# pinchy.net
KiCad netlist of a schematic drawn in EAGLE
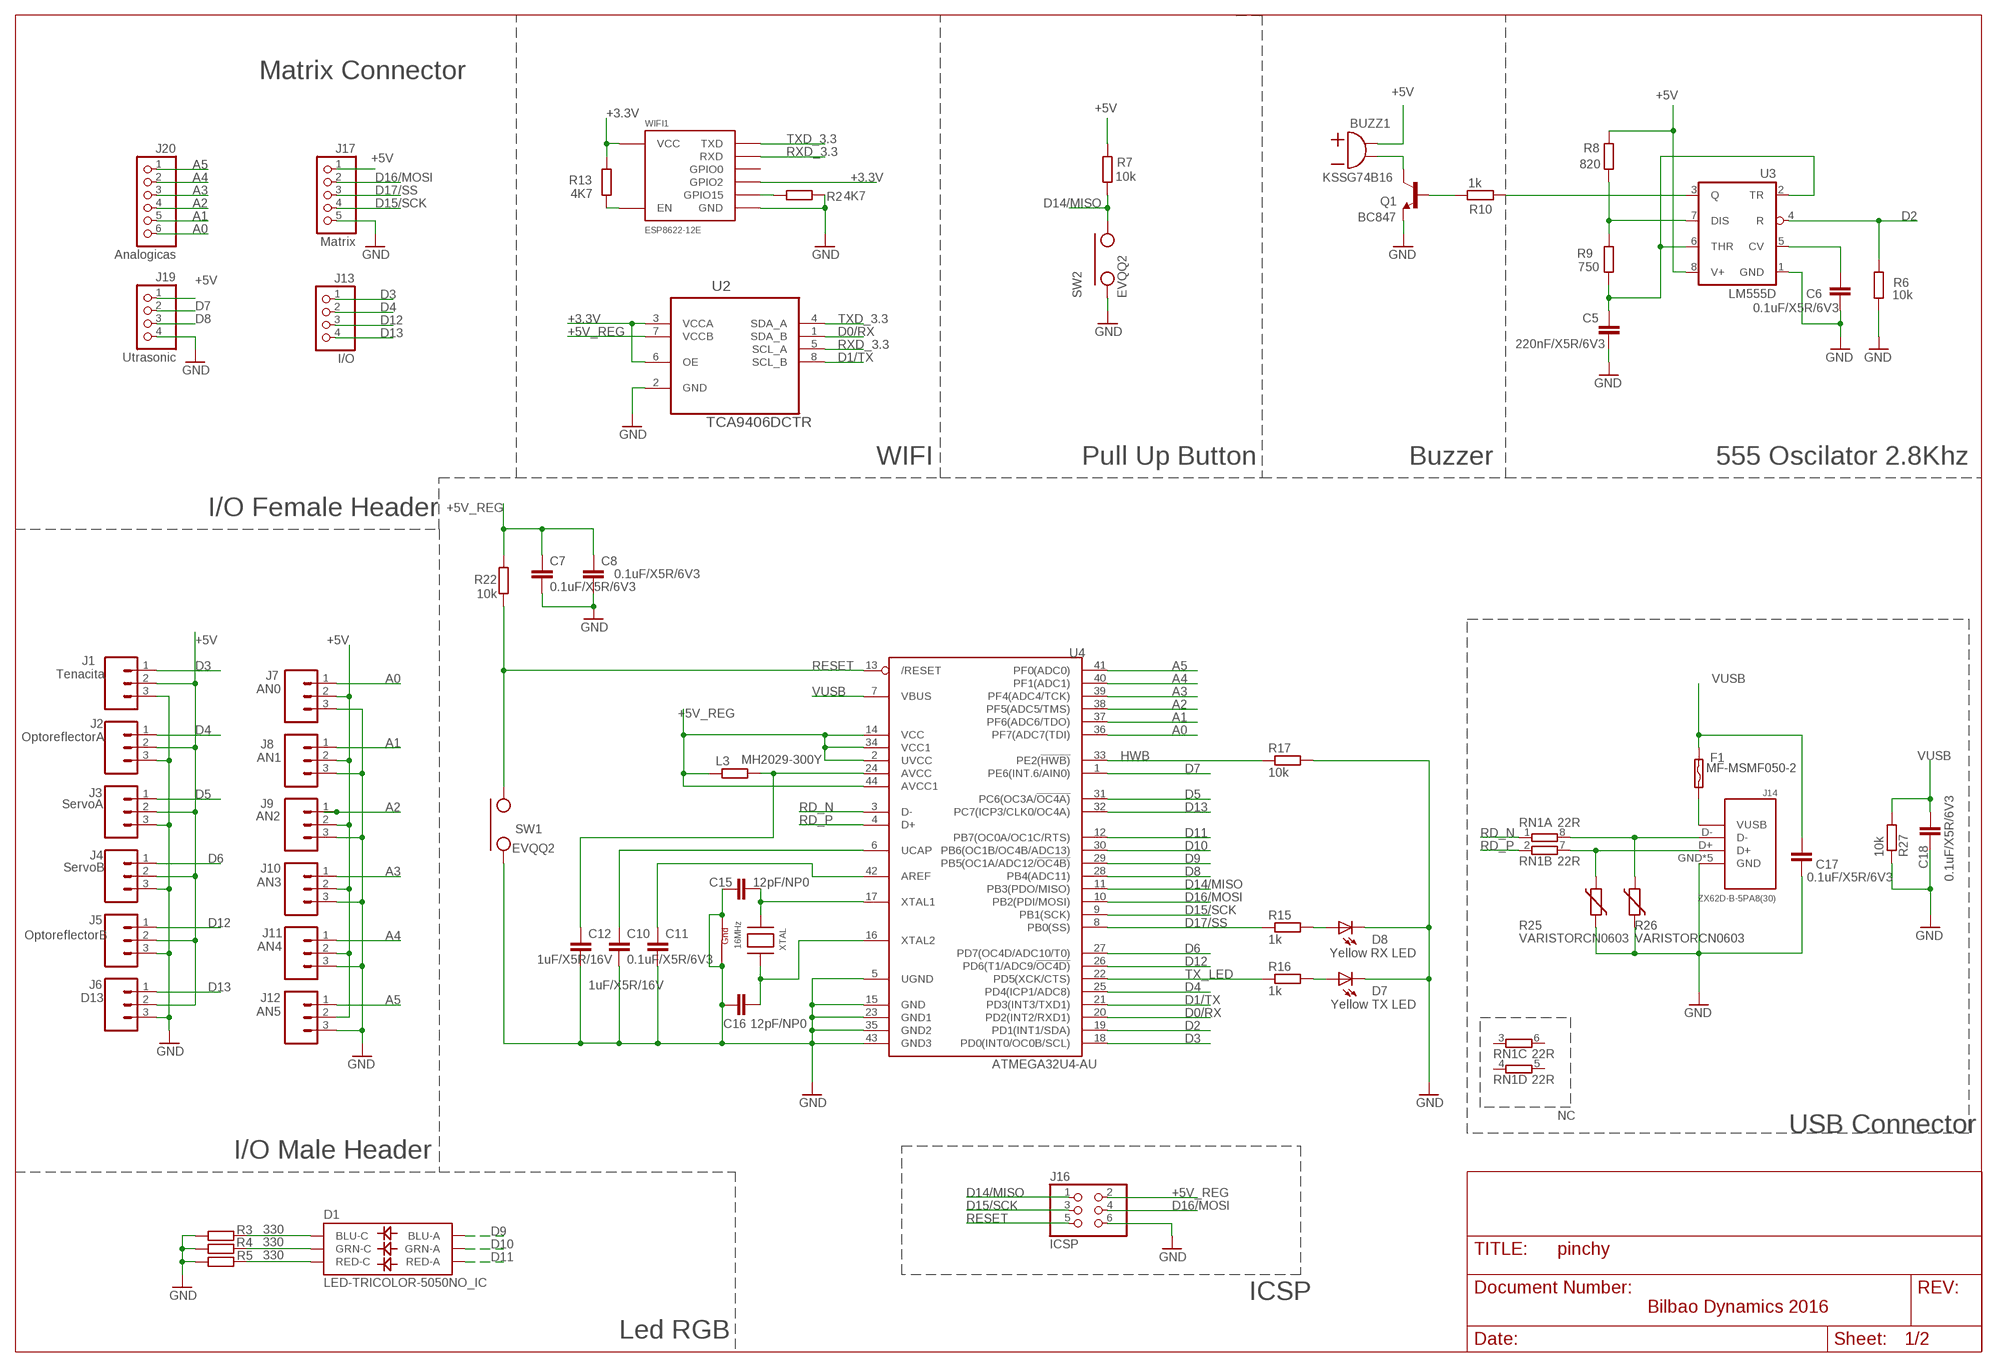
[diagram p0: schematic, sheet 1]
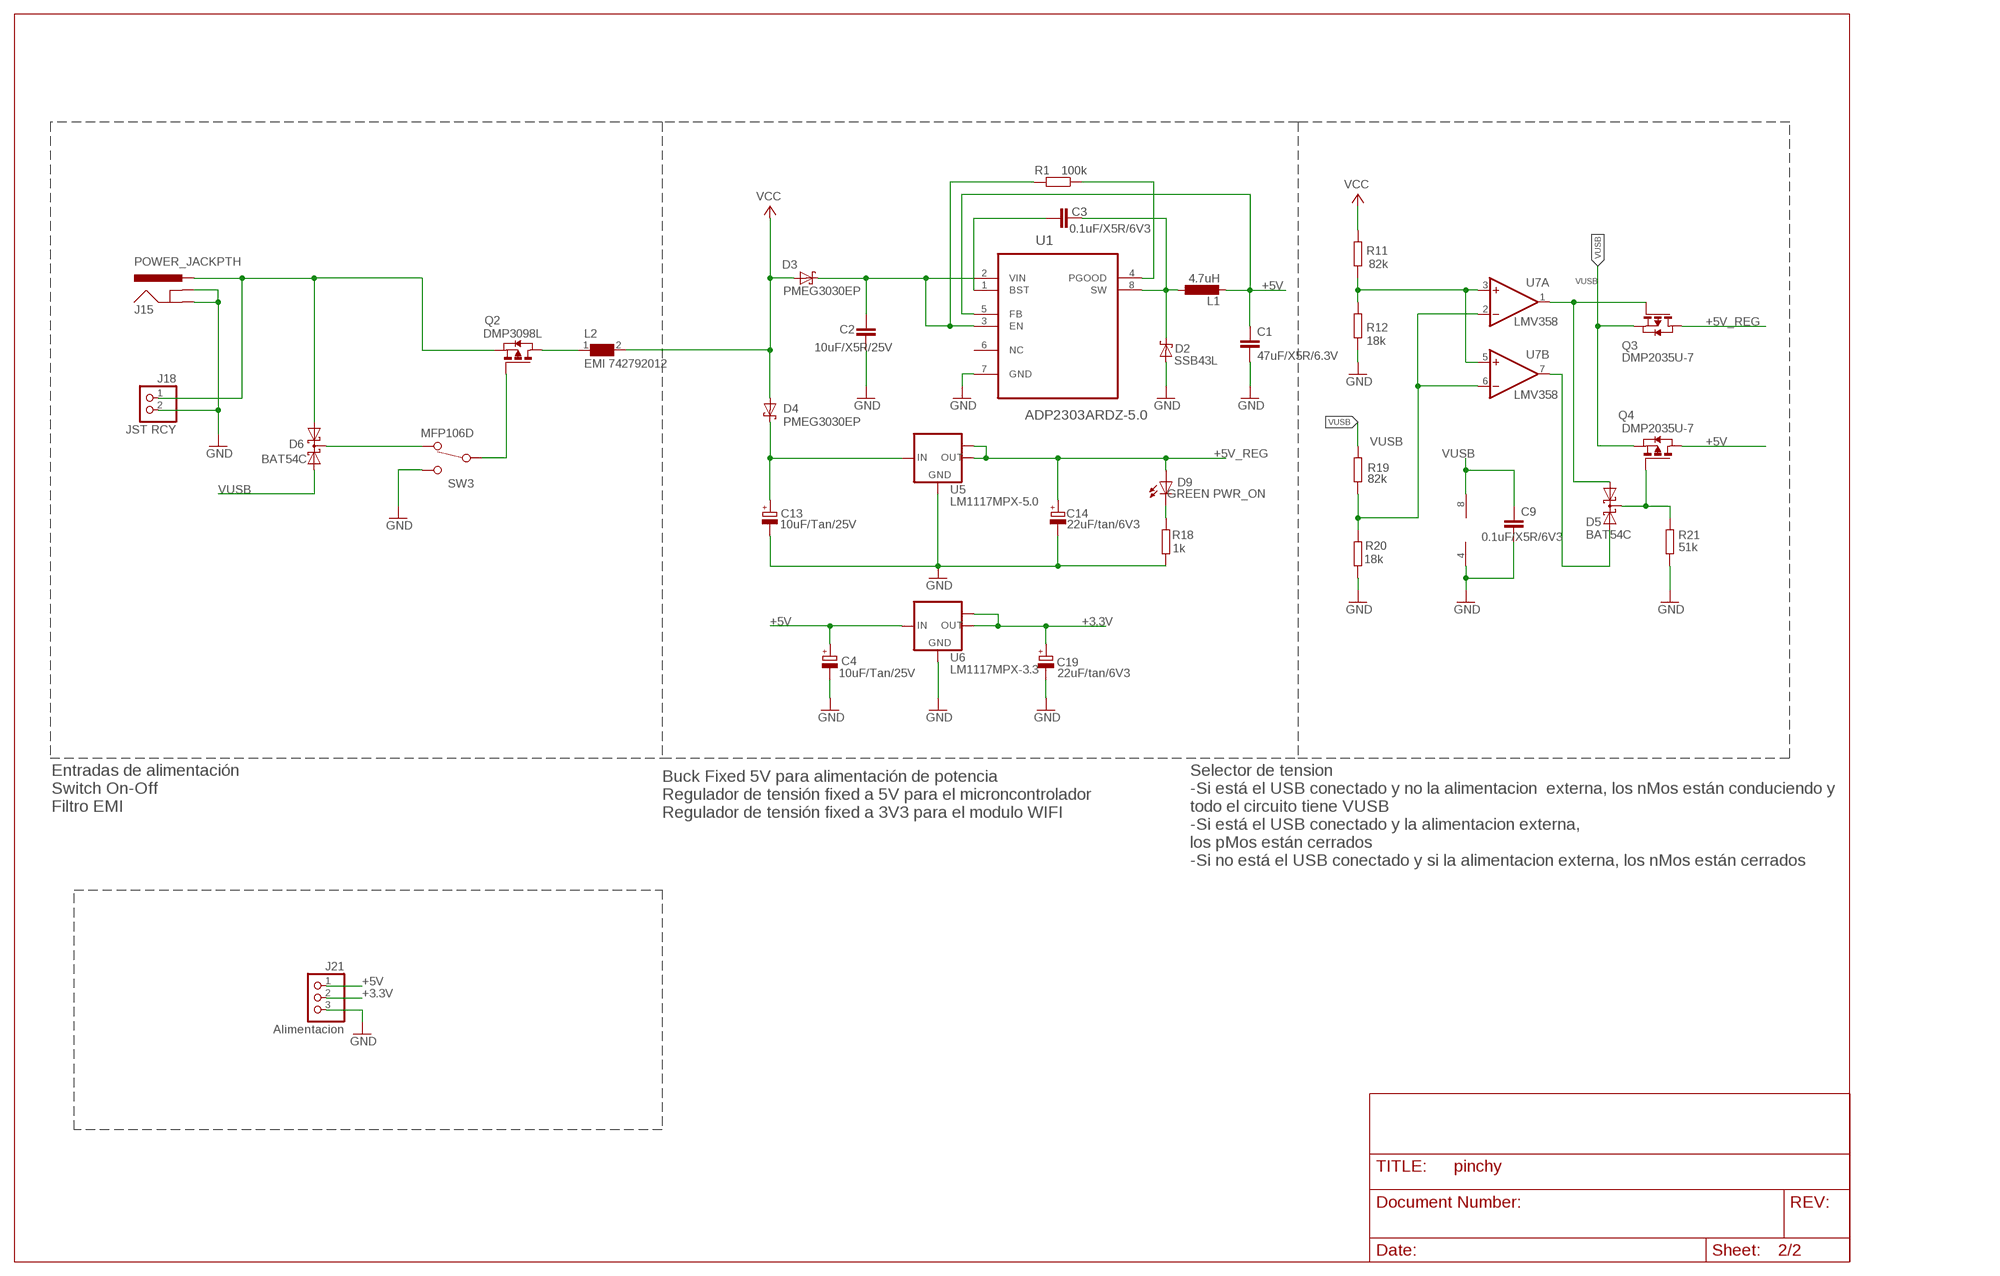
[diagram p1: schematic, sheet 2]

(export (version "E")
  (design (tool "Eeschema 10.0.6"))
  (components
    (comp (ref "C1")
      (value "47uF/X5R/6.3V")
      (footprint "eagle-import:C1210")
      (libsource (lib "eagle-import") (part "C-EUC1210"))
    )
    (comp (ref "C2")
      (value "10uF/X5R/25V")
      (footprint "eagle-import:C0805")
      (libsource (lib "eagle-import") (part "C-EUC0805"))
    )
    (comp (ref "C3")
      (value "0.1uF/X5R/6V3")
      (footprint "eagle-import:C0805")
      (libsource (lib "eagle-import") (part "C-EUC0805"))
    )
    (comp (ref "C4")
      (value "10uF/Tan/25V")
      (footprint "eagle-import:C1206-POL")
      (libsource (lib "eagle-import") (part "C1206-POL"))
    )
    (comp (ref "C9")
      (value "0.1uF/X5R/6V3")
      (footprint "eagle-import:C0805")
      (libsource (lib "eagle-import") (part "C-EUC0805"))
    )
    (comp (ref "C13")
      (value "10uF/Tan/25V")
      (footprint "eagle-import:C1206-POL")
      (libsource (lib "eagle-import") (part "C1206-POL"))
    )
    (comp (ref "C14")
      (value "22uF/tan/6V3")
      (footprint "eagle-import:C1206-POL")
      (libsource (lib "eagle-import") (part "C1206-POL"))
    )
    (comp (ref "C19")
      (value "22uF/tan/6V3")
      (footprint "eagle-import:C1206-POL")
      (libsource (lib "eagle-import") (part "C1206-POL"))
    )
    (comp (ref "D2")
      (value "SSB43L")
      (footprint "eagle-import:SSB43L")
      (libsource (lib "eagle-import") (part "SSB43L"))
    )
    (comp (ref "D3")
      (value "PMEG3030EP")
      (footprint "eagle-import:SMB")
      (libsource (lib "eagle-import") (part "SCHOTTKY-DIODESMD"))
    )
    (comp (ref "D4")
      (value "PMEG3030EP")
      (footprint "eagle-import:SMB")
      (libsource (lib "eagle-import") (part "SCHOTTKY-DIODESMD"))
    )
    (comp (ref "D5")
      (value "BAT54C")
      (footprint "eagle-import:SOT23")
      (libsource (lib "eagle-import") (part "BAT54C"))
    )
    (comp (ref "D6")
      (value "BAT54C")
      (footprint "eagle-import:SOT23")
      (libsource (lib "eagle-import") (part "BAT54C"))
    )
    (comp (ref "D9")
      (value "GREEN PWR_ON")
      (footprint "eagle-import:CHIPLED_0805")
      (libsource (lib "eagle-import") (part "LEDCHIPLED_0805"))
    )
    (comp (ref "J15")
      (value "POWER_JACKPTH")
      (footprint "eagle-import:POWER_JACK_PTH")
      (libsource (lib "eagle-import") (part "POWER_JACKPTH"))
    )
    (comp (ref "J18")
      (value "JST RCY")
      (footprint "eagle-import:1X02")
      (libsource (lib "eagle-import") (part "PINHD-1X2"))
    )
    (comp (ref "J21")
      (value "Alimentacion")
      (footprint "eagle-import:1X03")
      (libsource (lib "eagle-import") (part "PINHD-1X3"))
    )
    (comp (ref "L1")
      (value "4.7uH")
      (footprint "eagle-import:TDK_VLF10040T_4R7N5R4")
      (libsource (lib "eagle-import") (part "TDK_VLF10040T_4R7N5R4"))
    )
    (comp (ref "L2")
      (value "EMI 742792012")
      (footprint "eagle-import:0805")
      (fields (field (name "MPN") "742792012"))
      (libsource (lib "eagle-import") (part "WE-CBF_0805-742792012"))
    )
    (comp (ref "Q2")
      (value "DMP3098L")
      (footprint "eagle-import:SOT-23")
      (libsource (lib "eagle-import") (part "PMOSSOT23"))
    )
    (comp (ref "Q3")
      (value "DMP2035U-7")
      (footprint "eagle-import:SOT-23")
      (libsource (lib "eagle-import") (part "PMOSSOT23"))
    )
    (comp (ref "Q4")
      (value "DMP2035U-7")
      (footprint "eagle-import:SOT-23")
      (libsource (lib "eagle-import") (part "PMOSSOT23"))
    )
    (comp (ref "R1")
      (value "100k")
      (footprint "eagle-import:R0805")
      (libsource (lib "eagle-import") (part "R-EU_R0805"))
    )
    (comp (ref "R11")
      (value "82k")
      (footprint "eagle-import:R0805")
      (libsource (lib "eagle-import") (part "R-EU_R0805"))
    )
    (comp (ref "R12")
      (value "18k")
      (footprint "eagle-import:R0805")
      (libsource (lib "eagle-import") (part "R-EU_R0805"))
    )
    (comp (ref "R18")
      (value "1k")
      (footprint "eagle-import:R0805")
      (libsource (lib "eagle-import") (part "R-EU_R0805"))
    )
    (comp (ref "R19")
      (value "82k")
      (footprint "eagle-import:R0805")
      (libsource (lib "eagle-import") (part "R-EU_R0805"))
    )
    (comp (ref "R20")
      (value "18k")
      (footprint "eagle-import:R0805")
      (libsource (lib "eagle-import") (part "R-EU_R0805"))
    )
    (comp (ref "R21")
      (value "51k")
      (footprint "eagle-import:R0805")
      (libsource (lib "eagle-import") (part "R-EU_R0805"))
    )
    (comp (ref "SW3")
      (value "MFP106D")
      (footprint "eagle-import:MFP106D")
      (libsource (lib "eagle-import") (part "MFP106D"))
    )
    (comp (ref "U1")
      (value "ADP2303ARDZ-5.0")
      (footprint "eagle-import:SOIC127P600X175-9N")
      (libsource (lib "eagle-import") (part "ADP2303ARDZ-5.0"))
    )
    (comp (ref "U5")
      (value "LM1117MPX-5.0")
      (footprint "eagle-import:SOT223")
      (libsource (lib "eagle-import") (part "LM1117MPX-5.0"))
    )
    (comp (ref "U6")
      (value "LM1117MPX-3.3")
      (footprint "eagle-import:SOT223")
      (libsource (lib "eagle-import") (part "pinchy_LM1117MPX-3.3"))
    )
    (comp (ref "U7")
      (value "LMV358")
      (footprint "eagle-import:SO08")
      (libsource (lib "eagle-import") (part "LM358D"))
    )
    (comp (ref "BUZZ1")
      (value "KSSG74B16")
      (footprint "eagle-import:KSSG74B16")
      (libsource (lib "eagle-import") (part "KSSG74B16"))
    )
    (comp (ref "C5")
      (value "220nF/X5R/6V3")
      (footprint "eagle-import:C0805")
      (libsource (lib "eagle-import") (part "C-EUC0805"))
    )
    (comp (ref "C6")
      (value "0.1uF/X5R/6V3")
      (footprint "eagle-import:C0805")
      (libsource (lib "eagle-import") (part "C-EUC0805"))
    )
    (comp (ref "C7")
      (value "0.1uF/X5R/6V3")
      (footprint "eagle-import:C0805")
      (libsource (lib "eagle-import") (part "C-EUC0805"))
    )
    (comp (ref "C8")
      (value "0.1uF/X5R/6V3")
      (footprint "eagle-import:C0805")
      (libsource (lib "eagle-import") (part "C-EUC0805"))
    )
    (comp (ref "C10")
      (value "1uF/X5R/16V")
      (footprint "eagle-import:C1206")
      (libsource (lib "eagle-import") (part "C-EUC1206"))
    )
    (comp (ref "C11")
      (value "0.1uF/X5R/6V3")
      (footprint "eagle-import:C0805")
      (libsource (lib "eagle-import") (part "C-EUC0805"))
    )
    (comp (ref "C12")
      (value "1uF/X5R/16V")
      (footprint "eagle-import:C1206")
      (libsource (lib "eagle-import") (part "C-EUC1206"))
    )
    (comp (ref "C15")
      (value "12pF/NP0")
      (footprint "eagle-import:C0805")
      (libsource (lib "eagle-import") (part "C-EUC0805"))
    )
    (comp (ref "C16")
      (value "12pF/NP0")
      (footprint "eagle-import:C0805")
      (libsource (lib "eagle-import") (part "C-EUC0805"))
    )
    (comp (ref "C17")
      (value "0.1uF/X5R/6V3")
      (footprint "eagle-import:C1206")
      (libsource (lib "eagle-import") (part "C-EUC1206"))
    )
    (comp (ref "C18")
      (value "0.1uF/X5R/6V3")
      (footprint "eagle-import:C0805")
      (libsource (lib "eagle-import") (part "C-EUC0805"))
    )
    (comp (ref "D1")
      (value "LED-TRICOLOR-5050NO_IC")
      (footprint "eagle-import:LED-TRICOLOR-5050")
      (libsource (lib "eagle-import") (part "LED-TRICOLOR-5050NO_IC"))
    )
    (comp (ref "D7")
      (value "Yellow TX LED")
      (footprint "eagle-import:CHIPLED_0805")
      (libsource (lib "eagle-import") (part "LEDCHIPLED_0805"))
    )
    (comp (ref "D8")
      (value "Yellow RX LED")
      (footprint "eagle-import:CHIPLED_0805")
      (libsource (lib "eagle-import") (part "LEDCHIPLED_0805"))
    )
    (comp (ref "F1")
      (value "MF-MSMF050-2")
      (footprint "eagle-import:SMD050F")
      (libsource (lib "eagle-import") (part "SMDF260"))
    )
    (comp (ref "J1")
      (value "Tenacita")
      (footprint "eagle-import:1X03")
      (libsource (lib "eagle-import") (part "M03PTH"))
    )
    (comp (ref "J2")
      (value "OptoreflectorA")
      (footprint "eagle-import:1X03")
      (libsource (lib "eagle-import") (part "M03PTH"))
    )
    (comp (ref "J3")
      (value "ServoA")
      (footprint "eagle-import:1X03")
      (libsource (lib "eagle-import") (part "M03PTH"))
    )
    (comp (ref "J4")
      (value "ServoB")
      (footprint "eagle-import:1X03")
      (libsource (lib "eagle-import") (part "M03PTH"))
    )
    (comp (ref "J5")
      (value "OptoreflectorB")
      (footprint "eagle-import:1X03")
      (libsource (lib "eagle-import") (part "M03PTH"))
    )
    (comp (ref "J6")
      (value "D13")
      (footprint "eagle-import:1X03")
      (libsource (lib "eagle-import") (part "M03PTH"))
    )
    (comp (ref "J7")
      (value "AN0")
      (footprint "eagle-import:1X03")
      (libsource (lib "eagle-import") (part "M03PTH"))
    )
    (comp (ref "J8")
      (value "AN1")
      (footprint "eagle-import:1X03")
      (libsource (lib "eagle-import") (part "M03PTH"))
    )
    (comp (ref "J9")
      (value "AN2")
      (footprint "eagle-import:1X03")
      (libsource (lib "eagle-import") (part "M03PTH"))
    )
    (comp (ref "J10")
      (value "AN3")
      (footprint "eagle-import:1X03")
      (libsource (lib "eagle-import") (part "M03PTH"))
    )
    (comp (ref "J11")
      (value "AN4")
      (footprint "eagle-import:1X03")
      (libsource (lib "eagle-import") (part "M03PTH"))
    )
    (comp (ref "J12")
      (value "AN5")
      (footprint "eagle-import:1X03")
      (libsource (lib "eagle-import") (part "M03PTH"))
    )
    (comp (ref "J13")
      (value "I/O")
      (footprint "eagle-import:1X04")
      (libsource (lib "eagle-import") (part "PINHD-1X4"))
    )
    (comp (ref "J14")
      (value "ZX62D-B-5PA8(30)")
      (footprint "eagle-import:ZX62D-B-5PA8(30)")
      (libsource (lib "eagle-import") (part "ZX62D-B-5PA8(30)"))
    )
    (comp (ref "J16")
      (value "ICSP")
      (footprint "eagle-import:2X03")
      (libsource (lib "eagle-import") (part "PINHD-2X3"))
    )
    (comp (ref "J17")
      (value "Matrix")
      (footprint "eagle-import:1X05")
      (libsource (lib "eagle-import") (part "PINHD-1X5"))
    )
    (comp (ref "J19")
      (value "Utrasonic")
      (footprint "eagle-import:1X04")
      (libsource (lib "eagle-import") (part "PINHD-1X4"))
    )
    (comp (ref "J20")
      (value "Analogicas")
      (footprint "eagle-import:1X06")
      (libsource (lib "eagle-import") (part "PINHD-1X6"))
    )
    (comp (ref "L3")
      (value "MH2029-300Y")
      (footprint "eagle-import:R0805")
      (libsource (lib "eagle-import") (part "R-EU_R0805"))
    )
    (comp (ref "Q1")
      (value "BC847")
      (footprint "eagle-import:SOT23")
      (libsource (lib "eagle-import") (part "BC847"))
    )
    (comp (ref "R2")
      (value "4K7")
      (footprint "eagle-import:R0805")
      (libsource (lib "eagle-import") (part "R-EU_R0805"))
    )
    (comp (ref "R3")
      (value "330")
      (footprint "eagle-import:R0805")
      (libsource (lib "eagle-import") (part "R-EU_R0805"))
    )
    (comp (ref "R4")
      (value "330")
      (footprint "eagle-import:R0805")
      (libsource (lib "eagle-import") (part "R-EU_R0805"))
    )
    (comp (ref "R5")
      (value "330")
      (footprint "eagle-import:R0805")
      (libsource (lib "eagle-import") (part "R-EU_R0805"))
    )
    (comp (ref "R6")
      (value "10k")
      (footprint "eagle-import:R0805")
      (libsource (lib "eagle-import") (part "R-EU_R0805"))
    )
    (comp (ref "R7")
      (value "10k")
      (footprint "eagle-import:R0805")
      (libsource (lib "eagle-import") (part "R-EU_R0805"))
    )
    (comp (ref "R8")
      (value "820")
      (footprint "eagle-import:R0805")
      (libsource (lib "eagle-import") (part "R-EU_R0805"))
    )
    (comp (ref "R9")
      (value "750")
      (footprint "eagle-import:R0805")
      (libsource (lib "eagle-import") (part "R-EU_R0805"))
    )
    (comp (ref "R10")
      (value "1k")
      (footprint "eagle-import:R0805")
      (libsource (lib "eagle-import") (part "R-EU_R0805"))
    )
    (comp (ref "R13")
      (value "4K7")
      (footprint "eagle-import:R0805")
      (libsource (lib "eagle-import") (part "R-EU_R0805"))
    )
    (comp (ref "R15")
      (value "1k")
      (footprint "eagle-import:R0805")
      (libsource (lib "eagle-import") (part "R-EU_R0805"))
    )
    (comp (ref "R16")
      (value "1k")
      (footprint "eagle-import:R0805")
      (libsource (lib "eagle-import") (part "R-EU_R0805"))
    )
    (comp (ref "R17")
      (value "10k")
      (footprint "eagle-import:R0805")
      (libsource (lib "eagle-import") (part "R-EU_R0805"))
    )
    (comp (ref "R22")
      (value "10k")
      (footprint "eagle-import:R0805")
      (libsource (lib "eagle-import") (part "R-EU_R0805"))
    )
    (comp (ref "R25")
      (value "VARISTORCN0603")
      (footprint "eagle-import:CT_CN0603")
      (libsource (lib "eagle-import") (part "VARISTORCN0603"))
    )
    (comp (ref "R26")
      (value "VARISTORCN0603")
      (footprint "eagle-import:CT_CN0603")
      (libsource (lib "eagle-import") (part "VARISTORCN0603"))
    )
    (comp (ref "R27")
      (value "10k")
      (footprint "eagle-import:R0805")
      (libsource (lib "eagle-import") (part "R-EU_R0805"))
    )
    (comp (ref "RN1")
      (value "22R")
      (footprint "eagle-import:CAY16")
      (libsource (lib "eagle-import") (part "4R-NCAY16"))
    )
    (comp (ref "SW1")
      (value "EVQQ2")
      (footprint "eagle-import:JAEGGER_MKII_EVQQ2")
      (libsource (lib "eagle-import") (part "JAEGGER_MKII_EVQQ2"))
    )
    (comp (ref "SW2")
      (value "EVQQ2")
      (footprint "eagle-import:JAEGGER_MKII_EVQQ2")
      (libsource (lib "eagle-import") (part "JAEGGER_MKII_EVQQ2"))
    )
    (comp (ref "U2")
      (value "TCA9406DCTR")
      (footprint "eagle-import:SOP65P400X130-8N")
      (libsource (lib "eagle-import") (part "TCA9406DCTR"))
    )
    (comp (ref "U3")
      (value "LM555D")
      (footprint "eagle-import:SO08")
      (libsource (lib "eagle-import") (part "555DLM"))
    )
    (comp (ref "U4")
      (value "ATMEGA32U4-AU")
      (footprint "eagle-import:TQFP44")
      (libsource (lib "eagle-import") (part "ATMEGA32U4-AU"))
    )
    (comp (ref "WIFI1")
      (value "ESP8622-12E")
      (footprint "eagle-import:ESP8622-12E")
      (libsource (lib "eagle-import") (part "ESP8622-12E"))
    )
    (comp (ref "XTAL")
      (value "16MHz")
      (footprint "eagle-import:NX3225")
      (libsource (lib "eagle-import") (part "XTAL-4-3225"))
    )
  )
  (nets
    (net (code "1") (name "+3.3V") (class "Default")
      (node (ref "C19") (pin "2") (pinfunction "+_2") (pintype "passive"))
      (node (ref "J21") (pin "2") (pinfunction "2_2") (pintype "passive"))
      (node (ref "R13") (pin "2") (pinfunction "2_2") (pintype "passive"))
      (node (ref "U2") (pin "3") (pinfunction "VCCA_3") (pintype "power_in"))
      (node (ref "U2") (pin "6") (pinfunction "OE_6") (pintype "input"))
      (node (ref "U6") (pin "2") (pinfunction "OUT_2") (pintype "passive"))
      (node (ref "U6") (pin "TAB") (pinfunction "OUT1_TAB") (pintype "passive"))
      (node (ref "WIFI1") (pin "GPIO2") (pinfunction "GPIO2_GPIO2") (pintype "passive"))
      (node (ref "WIFI1") (pin "VCC") (pinfunction "VCC_VCC") (pintype "passive"))
    )
    (net (code "2") (name "+5V") (class "Default")
      (node (ref "BUZZ1") (pin "P$2") (pinfunction "2_P$2") (pintype "passive"))
      (node (ref "BUZZ1") (pin "P$3") (pinfunction "2_P$3") (pintype "passive"))
      (node (ref "C1") (pin "1") (pinfunction "1_1") (pintype "passive"))
      (node (ref "C4") (pin "2") (pinfunction "+_2") (pintype "passive"))
      (node (ref "J1") (pin "2") (pinfunction "2_2") (pintype "passive"))
      (node (ref "J10") (pin "2") (pinfunction "2_2") (pintype "passive"))
      (node (ref "J11") (pin "2") (pinfunction "2_2") (pintype "passive"))
      (node (ref "J12") (pin "2") (pinfunction "2_2") (pintype "passive"))
      (node (ref "J17") (pin "1") (pinfunction "1_1") (pintype "passive"))
      (node (ref "J19") (pin "1") (pinfunction "1_1") (pintype "passive"))
      (node (ref "J2") (pin "2") (pinfunction "2_2") (pintype "passive"))
      (node (ref "J21") (pin "1") (pinfunction "1_1") (pintype "passive"))
      (node (ref "J3") (pin "2") (pinfunction "2_2") (pintype "passive"))
      (node (ref "J4") (pin "2") (pinfunction "2_2") (pintype "passive"))
      (node (ref "J5") (pin "2") (pinfunction "2_2") (pintype "passive"))
      (node (ref "J6") (pin "2") (pinfunction "2_2") (pintype "passive"))
      (node (ref "J7") (pin "2") (pinfunction "2_2") (pintype "passive"))
      (node (ref "J8") (pin "2") (pinfunction "2_2") (pintype "passive"))
      (node (ref "J9") (pin "2") (pinfunction "2_2") (pintype "passive"))
      (node (ref "L1") (pin "2") (pinfunction "2_2") (pintype "passive"))
      (node (ref "Q4") (pin "1") (pinfunction "D_1") (pintype "passive"))
      (node (ref "R7") (pin "2") (pinfunction "2_2") (pintype "passive"))
      (node (ref "R8") (pin "2") (pinfunction "2_2") (pintype "passive"))
      (node (ref "U1") (pin "5") (pinfunction "FB_5") (pintype "input"))
      (node (ref "U3") (pin "8") (pinfunction "V+_8") (pintype "power_in"))
      (node (ref "U6") (pin "3") (pinfunction "IN_3") (pintype "input"))
    )
    (net (code "3") (name "+5V_REG") (class "Default")
      (node (ref "C14") (pin "2") (pinfunction "+_2") (pintype "passive"))
      (node (ref "C7") (pin "1") (pinfunction "1_1") (pintype "passive"))
      (node (ref "C8") (pin "1") (pinfunction "1_1") (pintype "passive"))
      (node (ref "D9") (pin "A") (pinfunction "A_A") (pintype "passive"))
      (node (ref "J16") (pin "2") (pinfunction "2_2") (pintype "passive"))
      (node (ref "L3") (pin "1") (pinfunction "1_1") (pintype "passive"))
      (node (ref "Q3") (pin "1") (pinfunction "D_1") (pintype "passive"))
      (node (ref "R22") (pin "2") (pinfunction "2_2") (pintype "passive"))
      (node (ref "U2") (pin "7") (pinfunction "VCCB_7") (pintype "power_in"))
      (node (ref "U4") (pin "14") (pinfunction "VCC_14") (pintype "bidirectional"))
      (node (ref "U4") (pin "2") (pinfunction "UVCC_2") (pintype "bidirectional"))
      (node (ref "U4") (pin "34") (pinfunction "VCC1_34") (pintype "bidirectional"))
      (node (ref "U4") (pin "44") (pinfunction "AVCC1_44") (pintype "bidirectional"))
      (node (ref "U5") (pin "2") (pinfunction "OUT_2") (pintype "passive"))
      (node (ref "U5") (pin "TAB") (pinfunction "OUT1_TAB") (pintype "passive"))
    )
    (net (code "4") (name "A0") (class "Default")
      (node (ref "J20") (pin "6") (pinfunction "6_6") (pintype "passive"))
      (node (ref "J7") (pin "1") (pinfunction "1_1") (pintype "passive"))
      (node (ref "U4") (pin "36") (pinfunction "PF7(ADC7(TDI)_36") (pintype "bidirectional"))
    )
    (net (code "5") (name "A1") (class "Default")
      (node (ref "J20") (pin "5") (pinfunction "5_5") (pintype "passive"))
      (node (ref "J8") (pin "1") (pinfunction "1_1") (pintype "passive"))
      (node (ref "U4") (pin "37") (pinfunction "PF6(ADC6/TDO)_37") (pintype "bidirectional"))
    )
    (net (code "6") (name "A2") (class "Default")
      (node (ref "J20") (pin "4") (pinfunction "4_4") (pintype "passive"))
      (node (ref "J9") (pin "1") (pinfunction "1_1") (pintype "passive"))
      (node (ref "U4") (pin "38") (pinfunction "PF5(ADC5/TMS)_38") (pintype "bidirectional"))
    )
    (net (code "7") (name "A3") (class "Default")
      (node (ref "J10") (pin "1") (pinfunction "1_1") (pintype "passive"))
      (node (ref "J20") (pin "3") (pinfunction "3_3") (pintype "passive"))
      (node (ref "U4") (pin "39") (pinfunction "PF4(ADC4/TCK)_39") (pintype "bidirectional"))
    )
    (net (code "8") (name "A4") (class "Default")
      (node (ref "J11") (pin "1") (pinfunction "1_1") (pintype "passive"))
      (node (ref "J20") (pin "2") (pinfunction "2_2") (pintype "passive"))
      (node (ref "U4") (pin "40") (pinfunction "PF1(ADC1)_40") (pintype "bidirectional"))
    )
    (net (code "9") (name "A5") (class "Default")
      (node (ref "J12") (pin "1") (pinfunction "1_1") (pintype "passive"))
      (node (ref "J20") (pin "1") (pinfunction "1_1") (pintype "passive"))
      (node (ref "U4") (pin "41") (pinfunction "PF0(ADC0)_41") (pintype "bidirectional"))
    )
    (net (code "10") (name "D0{slash}RX") (class "Default")
      (node (ref "U2") (pin "1") (pinfunction "SDA_B_1") (pintype "bidirectional"))
      (node (ref "U4") (pin "20") (pinfunction "PD2(INT2/RXD1)_20") (pintype "bidirectional"))
    )
    (net (code "11") (name "D1{slash}TX") (class "Default")
      (node (ref "U2") (pin "8") (pinfunction "SCL_B_8") (pintype "bidirectional"))
      (node (ref "U4") (pin "21") (pinfunction "PD3(INT3/TXD1)_21") (pintype "bidirectional"))
    )
    (net (code "12") (name "D2") (class "Default")
      (node (ref "R6") (pin "1") (pinfunction "1_1") (pintype "passive"))
      (node (ref "U3") (pin "4") (pinfunction "R_4") (pintype "input"))
      (node (ref "U4") (pin "19") (pinfunction "PD1(INT1/SDA)_19") (pintype "bidirectional"))
    )
    (net (code "13") (name "D3") (class "Default")
      (node (ref "J1") (pin "1") (pinfunction "1_1") (pintype "passive"))
      (node (ref "J13") (pin "1") (pinfunction "1_1") (pintype "passive"))
      (node (ref "U4") (pin "18") (pinfunction "PD0(INT0/OC0B/SCL)_18") (pintype "bidirectional"))
    )
    (net (code "14") (name "D4") (class "Default")
      (node (ref "J13") (pin "2") (pinfunction "2_2") (pintype "passive"))
      (node (ref "J2") (pin "1") (pinfunction "1_1") (pintype "passive"))
      (node (ref "U4") (pin "25") (pinfunction "PD4(ICP1/ADC8)_25") (pintype "bidirectional"))
    )
    (net (code "15") (name "D5") (class "Default")
      (node (ref "J3") (pin "1") (pinfunction "1_1") (pintype "passive"))
      (node (ref "U4") (pin "31") (pinfunction "PC6(OC3A/~{OC4A})_31") (pintype "bidirectional"))
    )
    (net (code "16") (name "D6") (class "Default")
      (node (ref "J4") (pin "1") (pinfunction "1_1") (pintype "passive"))
      (node (ref "U4") (pin "27") (pinfunction "PD7(OC4D/ADC10/T0)_27") (pintype "bidirectional"))
    )
    (net (code "17") (name "D7") (class "Default")
      (node (ref "J19") (pin "2") (pinfunction "2_2") (pintype "passive"))
      (node (ref "U4") (pin "1") (pinfunction "PE6(INT.6/AIN0)_1") (pintype "bidirectional"))
    )
    (net (code "18") (name "D8") (class "Default")
      (node (ref "J19") (pin "3") (pinfunction "3_3") (pintype "passive"))
      (node (ref "U4") (pin "28") (pinfunction "PB4(ADC11)_28") (pintype "bidirectional"))
    )
    (net (code "19") (name "D9") (class "Default")
      (node (ref "D1") (pin "3") (pinfunction "BLU-A_3") (pintype "bidirectional"))
      (node (ref "U4") (pin "29") (pinfunction "PB5(OC1A/ADC12/~{OC4B})_29") (pintype "bidirectional"))
    )
    (net (code "20") (name "D10") (class "Default")
      (node (ref "D1") (pin "1") (pinfunction "GRN-A_1") (pintype "bidirectional"))
      (node (ref "U4") (pin "30") (pinfunction "PB6(OC1B/OC4B/ADC13)_30") (pintype "bidirectional"))
    )
    (net (code "21") (name "D11") (class "Default")
      (node (ref "D1") (pin "2") (pinfunction "RED-A_2") (pintype "bidirectional"))
      (node (ref "U4") (pin "12") (pinfunction "PB7(OC0A/OC1C/RTS)_12") (pintype "bidirectional"))
    )
    (net (code "22") (name "D12") (class "Default")
      (node (ref "J13") (pin "3") (pinfunction "3_3") (pintype "passive"))
      (node (ref "J5") (pin "1") (pinfunction "1_1") (pintype "passive"))
      (node (ref "U4") (pin "26") (pinfunction "PD6(T1/ADC9/~{OC4D})_26") (pintype "bidirectional"))
    )
    (net (code "23") (name "D13") (class "Default")
      (node (ref "J13") (pin "4") (pinfunction "4_4") (pintype "passive"))
      (node (ref "J6") (pin "1") (pinfunction "1_1") (pintype "passive"))
      (node (ref "U4") (pin "32") (pinfunction "PC7(ICP3/CLK0/OC4A)_32") (pintype "bidirectional"))
    )
    (net (code "24") (name "D14{slash}MISO") (class "Default")
      (node (ref "J16") (pin "1") (pinfunction "1_1") (pintype "passive"))
      (node (ref "R7") (pin "1") (pinfunction "1_1") (pintype "passive"))
      (node (ref "SW2") (pin "P$1") (pinfunction "P$2_P$1") (pintype "passive"))
      (node (ref "SW2") (pin "P$4") (pinfunction "P$2_P$4") (pintype "passive"))
      (node (ref "U4") (pin "11") (pinfunction "PB3(PDO/MISO)_11") (pintype "bidirectional"))
    )
    (net (code "25") (name "D15{slash}SCK") (class "Default")
      (node (ref "J16") (pin "3") (pinfunction "3_3") (pintype "passive"))
      (node (ref "J17") (pin "4") (pinfunction "4_4") (pintype "passive"))
      (node (ref "U4") (pin "9") (pinfunction "PB1(SCK)_9") (pintype "bidirectional"))
    )
    (net (code "26") (name "D16{slash}MOSI") (class "Default")
      (node (ref "J16") (pin "4") (pinfunction "4_4") (pintype "passive"))
      (node (ref "J17") (pin "2") (pinfunction "2_2") (pintype "passive"))
      (node (ref "U4") (pin "10") (pinfunction "PB2(PDI/MOSI)_10") (pintype "bidirectional"))
    )
    (net (code "27") (name "D17{slash}SS") (class "Default")
      (node (ref "J17") (pin "3") (pinfunction "3_3") (pintype "passive"))
      (node (ref "R15") (pin "1") (pinfunction "1_1") (pintype "passive"))
      (node (ref "U4") (pin "8") (pinfunction "PB0(SS)_8") (pintype "bidirectional"))
    )
    (net (code "28") (name "GND") (class "Default")
      (node (ref "C1") (pin "2") (pinfunction "2_2") (pintype "passive"))
      (node (ref "C10") (pin "2") (pinfunction "2_2") (pintype "passive"))
      (node (ref "C11") (pin "2") (pinfunction "2_2") (pintype "passive"))
      (node (ref "C12") (pin "2") (pinfunction "2_2") (pintype "passive"))
      (node (ref "C13") (pin "1") (pinfunction "-_1") (pintype "passive"))
      (node (ref "C14") (pin "1") (pinfunction "-_1") (pintype "passive"))
      (node (ref "C15") (pin "2") (pinfunction "2_2") (pintype "passive"))
      (node (ref "C16") (pin "2") (pinfunction "2_2") (pintype "passive"))
      (node (ref "C17") (pin "2") (pinfunction "2_2") (pintype "passive"))
      (node (ref "C18") (pin "2") (pinfunction "2_2") (pintype "passive"))
      (node (ref "C19") (pin "1") (pinfunction "-_1") (pintype "passive"))
      (node (ref "C2") (pin "2") (pinfunction "2_2") (pintype "passive"))
      (node (ref "C4") (pin "1") (pinfunction "-_1") (pintype "passive"))
      (node (ref "C5") (pin "2") (pinfunction "2_2") (pintype "passive"))
      (node (ref "C6") (pin "2") (pinfunction "2_2") (pintype "passive"))
      (node (ref "C7") (pin "2") (pinfunction "2_2") (pintype "passive"))
      (node (ref "C8") (pin "2") (pinfunction "2_2") (pintype "passive"))
      (node (ref "C9") (pin "2") (pinfunction "2_2") (pintype "passive"))
      (node (ref "D2") (pin "2") (pinfunction "A_2") (pintype "passive"))
      (node (ref "D7") (pin "C") (pinfunction "C_C") (pintype "passive"))
      (node (ref "D8") (pin "C") (pinfunction "C_C") (pintype "passive"))
      (node (ref "J1") (pin "3") (pinfunction "3_3") (pintype "passive"))
      (node (ref "J10") (pin "3") (pinfunction "3_3") (pintype "passive"))
      (node (ref "J11") (pin "3") (pinfunction "3_3") (pintype "passive"))
      (node (ref "J12") (pin "3") (pinfunction "3_3") (pintype "passive"))
      (node (ref "J14") (pin "GND") (pinfunction "GND_GND") (pintype "passive"))
      (node (ref "J14") (pin "P$1") (pinfunction "GND_P$1") (pintype "passive"))
      (node (ref "J14") (pin "P$2") (pinfunction "GND_P$2") (pintype "passive"))
      (node (ref "J14") (pin "P$6") (pinfunction "GND_P$6") (pintype "passive"))
      (node (ref "J14") (pin "P$7") (pinfunction "GND_P$7") (pintype "passive"))
      (node (ref "J15") (pin "GND") (pinfunction "GND_GND") (pintype "bidirectional"))
      (node (ref "J15") (pin "GNDBREAK") (pinfunction "GNDBREAK_GNDBREAK") (pintype "bidirectional"))
      (node (ref "J16") (pin "6") (pinfunction "6_6") (pintype "passive"))
      (node (ref "J17") (pin "5") (pinfunction "5_5") (pintype "passive"))
      (node (ref "J18") (pin "2") (pinfunction "2_2") (pintype "passive"))
      (node (ref "J19") (pin "4") (pinfunction "4_4") (pintype "passive"))
      (node (ref "J2") (pin "3") (pinfunction "3_3") (pintype "passive"))
      (node (ref "J21") (pin "3") (pinfunction "3_3") (pintype "passive"))
      (node (ref "J3") (pin "3") (pinfunction "3_3") (pintype "passive"))
      (node (ref "J4") (pin "3") (pinfunction "3_3") (pintype "passive"))
      (node (ref "J5") (pin "3") (pinfunction "3_3") (pintype "passive"))
      (node (ref "J6") (pin "3") (pinfunction "3_3") (pintype "passive"))
      (node (ref "J7") (pin "3") (pinfunction "3_3") (pintype "passive"))
      (node (ref "J8") (pin "3") (pinfunction "3_3") (pintype "passive"))
      (node (ref "J9") (pin "3") (pinfunction "3_3") (pintype "passive"))
      (node (ref "Q1") (pin "2") (pinfunction "E_2") (pintype "passive"))
      (node (ref "R12") (pin "1") (pinfunction "1_1") (pintype "passive"))
      (node (ref "R17") (pin "2") (pinfunction "2_2") (pintype "passive"))
      (node (ref "R18") (pin "1") (pinfunction "1_1") (pintype "passive"))
      (node (ref "R2") (pin "2") (pinfunction "2_2") (pintype "passive"))
      (node (ref "R20") (pin "1") (pinfunction "1_1") (pintype "passive"))
      (node (ref "R21") (pin "1") (pinfunction "1_1") (pintype "passive"))
      (node (ref "R25") (pin "1") (pinfunction "1_1") (pintype "passive"))
      (node (ref "R26") (pin "1") (pinfunction "1_1") (pintype "passive"))
      (node (ref "R27") (pin "1") (pinfunction "1_1") (pintype "passive"))
      (node (ref "R3") (pin "1") (pinfunction "1_1") (pintype "passive"))
      (node (ref "R4") (pin "1") (pinfunction "1_1") (pintype "passive"))
      (node (ref "R5") (pin "1") (pinfunction "1_1") (pintype "passive"))
      (node (ref "R6") (pin "2") (pinfunction "2_2") (pintype "passive"))
      (node (ref "SW1") (pin "P$2") (pinfunction "P$1_P$2") (pintype "passive"))
      (node (ref "SW1") (pin "P$3") (pinfunction "P$1_P$3") (pintype "passive"))
      (node (ref "SW2") (pin "P$2") (pinfunction "P$1_P$2") (pintype "passive"))
      (node (ref "SW2") (pin "P$3") (pinfunction "P$1_P$3") (pintype "passive"))
      (node (ref "SW3") (pin "2") (pinfunction "2_2") (pintype "passive"))
      (node (ref "U1") (pin "7") (pinfunction "GND_7") (pintype "passive"))
      (node (ref "U2") (pin "2") (pinfunction "GND_2") (pintype "power_in"))
      (node (ref "U3") (pin "1") (pinfunction "GND_1") (pintype "power_in"))
      (node (ref "U4") (pin "15") (pinfunction "GND_15") (pintype "bidirectional"))
      (node (ref "U4") (pin "23") (pinfunction "GND1_23") (pintype "bidirectional"))
      (node (ref "U4") (pin "35") (pinfunction "GND2_35") (pintype "bidirectional"))
      (node (ref "U4") (pin "43") (pinfunction "GND3_43") (pintype "bidirectional"))
      (node (ref "U4") (pin "5") (pinfunction "UGND_5") (pintype "bidirectional"))
      (node (ref "U5") (pin "1") (pinfunction "GND_1") (pintype "input"))
      (node (ref "U6") (pin "1") (pinfunction "GND_1") (pintype "input"))
      (node (ref "U7") (pin "4") (pinfunction "V-_4") (pintype "power_in"))
      (node (ref "WIFI1") (pin "GND") (pinfunction "GND_GND") (pintype "passive"))
      (node (ref "XTAL") (pin "2") (pinfunction "G2_2") (pintype "power_in"))
      (node (ref "XTAL") (pin "4") (pinfunction "G1_4") (pintype "power_in"))
    )
    (net (code "29") (name "HWB") (class "Default")
      (node (ref "R17") (pin "1") (pinfunction "1_1") (pintype "passive"))
      (node (ref "U4") (pin "33") (pinfunction "PE2(~{HWB})_33") (pintype "bidirectional"))
    )
    (net (code "30") (name "Net-(C13-+)") (class "Default")
      (node (ref "C13") (pin "2") (pinfunction "+_2") (pintype "passive"))
      (node (ref "D4") (pin "C") (pinfunction "C_C") (pintype "passive"))
      (node (ref "U5") (pin "3") (pinfunction "IN_3") (pintype "input"))
    )
    (net (code "31") (name "Net-(D1-BLU-C)") (class "Default")
      (node (ref "D1") (pin "4") (pinfunction "BLU-C_4") (pintype "bidirectional"))
      (node (ref "R3") (pin "2") (pinfunction "2_2") (pintype "passive"))
    )
    (net (code "32") (name "Net-(D1-GRN-C)") (class "Default")
      (node (ref "D1") (pin "6") (pinfunction "GRN-C_6") (pintype "bidirectional"))
      (node (ref "R4") (pin "2") (pinfunction "2_2") (pintype "passive"))
    )
    (net (code "33") (name "Net-(D1-RED-C)") (class "Default")
      (node (ref "D1") (pin "5") (pinfunction "RED-C_5") (pintype "bidirectional"))
      (node (ref "R5") (pin "2") (pinfunction "2_2") (pintype "passive"))
    )
    (net (code "34") (name "Net-(D2-C)") (class "Default")
      (node (ref "C3") (pin "2") (pinfunction "2_2") (pintype "passive"))
      (node (ref "D2") (pin "1") (pinfunction "C_1") (pintype "passive"))
      (node (ref "L1") (pin "1") (pinfunction "1_1") (pintype "passive"))
      (node (ref "U1") (pin "8") (pinfunction "SW_8") (pintype "output"))
    )
    (net (code "35") (name "Net-(D5-A1)") (class "Default")
      (node (ref "D5") (pin "1") (pinfunction "A1_1") (pintype "passive"))
      (node (ref "Q3") (pin "3") (pinfunction "G_3") (pintype "passive"))
      (node (ref "U7") (pin "1") (pinfunction "OUT_1") (pintype "output"))
    )
    (net (code "36") (name "Net-(D5-A2)") (class "Default")
      (node (ref "D5") (pin "2") (pinfunction "A2_2") (pintype "passive"))
      (node (ref "U7") (pin "7") (pinfunction "OUT_7") (pintype "output"))
    )
    (net (code "37") (name "Net-(D5-CC)") (class "Default")
      (node (ref "D5") (pin "3") (pinfunction "CC_3") (pintype "passive"))
      (node (ref "Q4") (pin "3") (pinfunction "G_3") (pintype "passive"))
      (node (ref "R21") (pin "2") (pinfunction "2_2") (pintype "passive"))
    )
    (net (code "38") (name "Net-(D6-A1)") (class "Default")
      (node (ref "D6") (pin "1") (pinfunction "A1_1") (pintype "passive"))
      (node (ref "J15") (pin "PWR") (pinfunction "PWR_PWR") (pintype "bidirectional"))
      (node (ref "J18") (pin "1") (pinfunction "1_1") (pintype "passive"))
      (node (ref "Q2") (pin "2") (pinfunction "S_2") (pintype "passive"))
    )
    (net (code "39") (name "Net-(D6-CC)") (class "Default")
      (node (ref "D6") (pin "3") (pinfunction "CC_3") (pintype "passive"))
      (node (ref "SW3") (pin "1") (pinfunction "1_1") (pintype "passive"))
    )
    (net (code "40") (name "Net-(D7-PadA)") (class "Default")
      (node (ref "D7") (pin "A") (pinfunction "A_A") (pintype "passive"))
      (node (ref "R16") (pin "2") (pinfunction "2_2") (pintype "passive"))
    )
    (net (code "41") (name "Net-(D8-PadA)") (class "Default")
      (node (ref "D8") (pin "A") (pinfunction "A_A") (pintype "passive"))
      (node (ref "R15") (pin "2") (pinfunction "2_2") (pintype "passive"))
    )
    (net (code "42") (name "Net-(D9-PadC)") (class "Default")
      (node (ref "D9") (pin "C") (pinfunction "C_C") (pintype "passive"))
      (node (ref "R18") (pin "2") (pinfunction "2_2") (pintype "passive"))
    )
    (net (code "43") (name "Net-(F1-Pad1)") (class "Default")
      (node (ref "F1") (pin "1") (pinfunction "1_1") (pintype "passive"))
      (node (ref "J14") (pin "VUSB") (pinfunction "VUSB_VUSB") (pintype "passive"))
    )
    (net (code "44") (name "Net-(Q1-B)") (class "Default")
      (node (ref "Q1") (pin "1") (pinfunction "B_1") (pintype "passive"))
      (node (ref "R10") (pin "1") (pinfunction "1_1") (pintype "passive"))
    )
    (net (code "45") (name "Net-(Q1-C)") (class "Default")
      (node (ref "BUZZ1") (pin "P$1") (pinfunction "1_P$1") (pintype "passive"))
      (node (ref "BUZZ1") (pin "P$4") (pinfunction "1_P$4") (pintype "passive"))
      (node (ref "Q1") (pin "3") (pinfunction "C_3") (pintype "passive"))
    )
    (net (code "46") (name "Net-(Q2-D)") (class "Default")
      (node (ref "L2") (pin "1") (pinfunction "1_1") (pintype "passive"))
      (node (ref "Q2") (pin "1") (pinfunction "D_1") (pintype "passive"))
    )
    (net (code "47") (name "Net-(Q2-G)") (class "Default")
      (node (ref "Q2") (pin "3") (pinfunction "G_3") (pintype "passive"))
      (node (ref "SW3") (pin "COM") (pinfunction "COM_COM") (pintype "passive"))
    )
    (net (code "48") (name "Net-(R2-Pad1)") (class "Default")
      (node (ref "R2") (pin "1") (pinfunction "1_1") (pintype "passive"))
      (node (ref "WIFI1") (pin "GPIO15") (pinfunction "GPIO15_GPIO15") (pintype "passive"))
    )
    (net (code "49") (name "Net-(R13-Pad1)") (class "Default")
      (node (ref "R13") (pin "1") (pinfunction "1_1") (pintype "passive"))
      (node (ref "WIFI1") (pin "EN") (pinfunction "EN_EN") (pintype "passive"))
    )
    (net (code "50") (name "Net-(RN1A-2)") (class "Default")
      (node (ref "J14") (pin "D-") (pinfunction "D-_D-") (pintype "passive"))
      (node (ref "R26") (pin "2") (pinfunction "2_2") (pintype "passive"))
      (node (ref "RN1") (pin "8") (pinfunction "2_8") (pintype "passive"))
    )
    (net (code "51") (name "Net-(RN1B-2)") (class "Default")
      (node (ref "J14") (pin "D+") (pinfunction "D+_D+") (pintype "passive"))
      (node (ref "R25") (pin "2") (pinfunction "2_2") (pintype "passive"))
      (node (ref "RN1") (pin "7") (pinfunction "2_7") (pintype "passive"))
    )
    (net (code "52") (name "Net-(U1-BST)") (class "Default")
      (node (ref "C3") (pin "1") (pinfunction "1_1") (pintype "passive"))
      (node (ref "U1") (pin "1") (pinfunction "BST_1") (pintype "power_in"))
    )
    (net (code "53") (name "Net-(U1-EN)") (class "Default")
      (node (ref "C2") (pin "1") (pinfunction "1_1") (pintype "passive"))
      (node (ref "D3") (pin "C") (pinfunction "C_C") (pintype "passive"))
      (node (ref "R1") (pin "2") (pinfunction "2_2") (pintype "passive"))
      (node (ref "U1") (pin "2") (pinfunction "VIN_2") (pintype "power_in"))
      (node (ref "U1") (pin "3") (pinfunction "EN_3") (pintype "input"))
    )
    (net (code "54") (name "Net-(U1-PGOOD)") (class "Default")
      (node (ref "R1") (pin "1") (pinfunction "1_1") (pintype "passive"))
      (node (ref "U1") (pin "4") (pinfunction "PGOOD_4") (pintype "output"))
    )
    (net (code "55") (name "Net-(U3-CV)") (class "Default")
      (node (ref "C6") (pin "1") (pinfunction "1_1") (pintype "passive"))
      (node (ref "U3") (pin "5") (pinfunction "CV_5") (pintype "input"))
    )
    (net (code "56") (name "Net-(U3-DIS)") (class "Default")
      (node (ref "R8") (pin "1") (pinfunction "1_1") (pintype "passive"))
      (node (ref "R9") (pin "2") (pinfunction "2_2") (pintype "passive"))
      (node (ref "U3") (pin "7") (pinfunction "DIS_7") (pintype "input"))
    )
    (net (code "57") (name "Net-(U3-Q)") (class "Default")
      (node (ref "R10") (pin "2") (pinfunction "2_2") (pintype "passive"))
      (node (ref "U3") (pin "3") (pinfunction "Q_3") (pintype "output"))
    )
    (net (code "58") (name "Net-(U3-THR)") (class "Default")
      (node (ref "C5") (pin "1") (pinfunction "1_1") (pintype "passive"))
      (node (ref "R9") (pin "1") (pinfunction "1_1") (pintype "passive"))
      (node (ref "U3") (pin "2") (pinfunction "TR_2") (pintype "input"))
      (node (ref "U3") (pin "6") (pinfunction "THR_6") (pintype "input"))
    )
    (net (code "59") (name "Net-(U4-AREF)") (class "Default")
      (node (ref "C11") (pin "1") (pinfunction "1_1") (pintype "passive"))
      (node (ref "U4") (pin "42") (pinfunction "AREF_42") (pintype "bidirectional"))
    )
    (net (code "60") (name "Net-(U4-AVCC)") (class "Default")
      (node (ref "C12") (pin "1") (pinfunction "1_1") (pintype "passive"))
      (node (ref "L3") (pin "2") (pinfunction "2_2") (pintype "passive"))
      (node (ref "U4") (pin "24") (pinfunction "AVCC_24") (pintype "bidirectional"))
    )
    (net (code "61") (name "Net-(U4-UCAP)") (class "Default")
      (node (ref "C10") (pin "1") (pinfunction "1_1") (pintype "passive"))
      (node (ref "U4") (pin "6") (pinfunction "UCAP_6") (pintype "bidirectional"))
    )
    (net (code "62") (name "Net-(U4-XTAL1)") (class "Default")
      (node (ref "C15") (pin "1") (pinfunction "1_1") (pintype "passive"))
      (node (ref "U4") (pin "17") (pinfunction "XTAL1_17") (pintype "bidirectional"))
      (node (ref "XTAL") (pin "1") (pinfunction "X1_1") (pintype "bidirectional"))
    )
    (net (code "63") (name "Net-(U4-XTAL2)") (class "Default")
      (node (ref "C16") (pin "1") (pinfunction "1_1") (pintype "passive"))
      (node (ref "U4") (pin "16") (pinfunction "XTAL2_16") (pintype "bidirectional"))
      (node (ref "XTAL") (pin "3") (pinfunction "X2_3") (pintype "bidirectional"))
    )
    (net (code "64") (name "Net-(U7A-+IN)") (class "Default")
      (node (ref "R11") (pin "1") (pinfunction "1_1") (pintype "passive"))
      (node (ref "R12") (pin "2") (pinfunction "2_2") (pintype "passive"))
      (node (ref "U7") (pin "3") (pinfunction "+IN_3") (pintype "input"))
      (node (ref "U7") (pin "5") (pinfunction "+IN_5") (pintype "input"))
    )
    (net (code "65") (name "Net-(U7A--IN)") (class "Default")
      (node (ref "R19") (pin "1") (pinfunction "1_1") (pintype "passive"))
      (node (ref "R20") (pin "2") (pinfunction "2_2") (pintype "passive"))
      (node (ref "U7") (pin "2") (pinfunction "-IN_2") (pintype "input"))
      (node (ref "U7") (pin "6") (pinfunction "-IN_6") (pintype "input"))
    )
    (net (code "66") (name "RD_N") (class "Default")
      (node (ref "RN1") (pin "1") (pinfunction "1_1") (pintype "passive"))
      (node (ref "U4") (pin "3") (pinfunction "D-_3") (pintype "bidirectional"))
    )
    (net (code "67") (name "RD_P") (class "Default")
      (node (ref "RN1") (pin "2") (pinfunction "1_2") (pintype "passive"))
      (node (ref "U4") (pin "4") (pinfunction "D+_4") (pintype "bidirectional"))
    )
    (net (code "68") (name "RESET") (class "Default")
      (node (ref "J16") (pin "5") (pinfunction "5_5") (pintype "passive"))
      (node (ref "R22") (pin "1") (pinfunction "1_1") (pintype "passive"))
      (node (ref "SW1") (pin "P$1") (pinfunction "P$2_P$1") (pintype "passive"))
      (node (ref "SW1") (pin "P$4") (pinfunction "P$2_P$4") (pintype "passive"))
      (node (ref "U4") (pin "13") (pinfunction "/RESET_13") (pintype "bidirectional"))
    )
    (net (code "69") (name "RXD_3.3") (class "Default")
      (node (ref "U2") (pin "5") (pinfunction "SCL_A_5") (pintype "bidirectional"))
      (node (ref "WIFI1") (pin "RXD") (pinfunction "RXD_RXD") (pintype "passive"))
    )
    (net (code "70") (name "TXD_3.3") (class "Default")
      (node (ref "U2") (pin "4") (pinfunction "SDA_A_4") (pintype "bidirectional"))
      (node (ref "WIFI1") (pin "TXD") (pinfunction "TXD_TXD") (pintype "passive"))
    )
    (net (code "71") (name "TX_LED") (class "Default")
      (node (ref "R16") (pin "1") (pinfunction "1_1") (pintype "passive"))
      (node (ref "U4") (pin "22") (pinfunction "PD5(XCK/CTS)_22") (pintype "bidirectional"))
    )
    (net (code "72") (name "VCC") (class "Default")
      (node (ref "D3") (pin "A") (pinfunction "A_A") (pintype "passive"))
      (node (ref "D4") (pin "A") (pinfunction "A_A") (pintype "passive"))
      (node (ref "L2") (pin "2") (pinfunction "2_2") (pintype "passive"))
      (node (ref "R11") (pin "2") (pinfunction "2_2") (pintype "passive"))
    )
    (net (code "73") (name "VUSB") (class "Default")
      (node (ref "C17") (pin "1") (pinfunction "1_1") (pintype "passive"))
      (node (ref "C18") (pin "1") (pinfunction "1_1") (pintype "passive"))
      (node (ref "C9") (pin "1") (pinfunction "1_1") (pintype "passive"))
      (node (ref "D6") (pin "2") (pinfunction "A2_2") (pintype "passive"))
      (node (ref "F1") (pin "2") (pinfunction "2_2") (pintype "passive"))
      (node (ref "Q3") (pin "2") (pinfunction "S_2") (pintype "passive"))
      (node (ref "Q4") (pin "2") (pinfunction "S_2") (pintype "passive"))
      (node (ref "R19") (pin "2") (pinfunction "2_2") (pintype "passive"))
      (node (ref "R27") (pin "2") (pinfunction "2_2") (pintype "passive"))
      (node (ref "U4") (pin "7") (pinfunction "VBUS_7") (pintype "bidirectional"))
      (node (ref "U7") (pin "8") (pinfunction "V+_8") (pintype "power_in"))
    )
    (net (code "74") (name "unconnected-(RN1C-1-Pad3)") (class "Default")
      (node (ref "RN1") (pin "3") (pinfunction "1_3") (pintype "passive"))
    )
    (net (code "75") (name "unconnected-(RN1C-2-Pad6)") (class "Default")
      (node (ref "RN1") (pin "6") (pinfunction "2_6") (pintype "passive"))
    )
    (net (code "76") (name "unconnected-(RN1D-1-Pad4)") (class "Default")
      (node (ref "RN1") (pin "4") (pinfunction "1_4") (pintype "passive"))
    )
    (net (code "77") (name "unconnected-(RN1D-2-Pad5)") (class "Default")
      (node (ref "RN1") (pin "5") (pinfunction "2_5") (pintype "passive"))
    )
    (net (code "78") (name "unconnected-(U1-NC-Pad6)") (class "Default")
      (node (ref "U1") (pin "6") (pinfunction "NC_6") (pintype "no_connect"))
    )
    (net (code "79") (name "unconnected-(WIFI1-PadGPIO0)") (class "Default")
      (node (ref "WIFI1") (pin "GPIO0") (pinfunction "GPIO0_GPIO0") (pintype "passive"))
    )
  )
)
